# PR9003.net
KiCad netlist of a schematic drawn in EAGLE
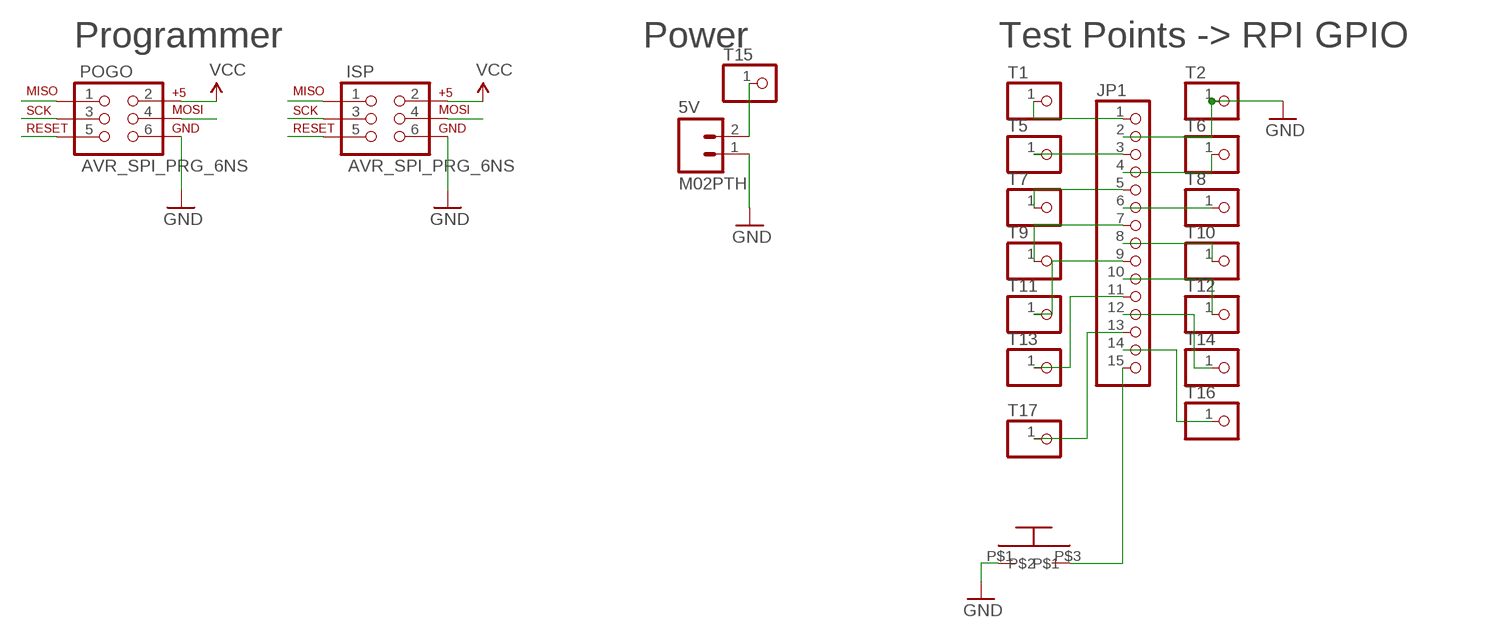
[diagram p0: schematic, sheet 1]

(export (version "E")
  (design (tool "Eeschema 10.0.6"))
  (components
    (comp (ref "5V")
      (value "M02PTH")
      (footprint "eagle-import:1X02")
      (libsource (lib "eagle-import") (part "M02PTH"))
    )
    (comp (ref "ISP")
      (value "AVR_SPI_PRG_6NS")
      (footprint "eagle-import:2X3-NS")
      (libsource (lib "eagle-import") (part "AVR_SPI_PRG_6NS"))
    )
    (comp (ref "JP1")
      (value "PINHD-1X15")
      (footprint "eagle-import:1X15")
      (libsource (lib "eagle-import") (part "PINHD-1X15"))
    )
    (comp (ref "POGO")
      (value "AVR_SPI_PRG_6NS")
      (footprint "eagle-import:2X3-NS")
      (libsource (lib "eagle-import") (part "AVR_SPI_PRG_6NS"))
    )
    (comp (ref "T1")
      (value "PINHD-1X1")
      (footprint "eagle-import:1X01")
      (libsource (lib "eagle-import") (part "PINHD-1X1"))
    )
    (comp (ref "T2")
      (value "PINHD-1X1")
      (footprint "eagle-import:1X01")
      (libsource (lib "eagle-import") (part "PINHD-1X1"))
    )
    (comp (ref "T5")
      (value "PINHD-1X1")
      (footprint "eagle-import:1X01")
      (libsource (lib "eagle-import") (part "PINHD-1X1"))
    )
    (comp (ref "T6")
      (value "PINHD-1X1")
      (footprint "eagle-import:1X01")
      (libsource (lib "eagle-import") (part "PINHD-1X1"))
    )
    (comp (ref "T7")
      (value "PINHD-1X1")
      (footprint "eagle-import:1X01")
      (libsource (lib "eagle-import") (part "PINHD-1X1"))
    )
    (comp (ref "T8")
      (value "PINHD-1X1")
      (footprint "eagle-import:1X01")
      (libsource (lib "eagle-import") (part "PINHD-1X1"))
    )
    (comp (ref "T9")
      (value "PINHD-1X1")
      (footprint "eagle-import:1X01")
      (libsource (lib "eagle-import") (part "PINHD-1X1"))
    )
    (comp (ref "T10")
      (value "PINHD-1X1")
      (footprint "eagle-import:1X01")
      (libsource (lib "eagle-import") (part "PINHD-1X1"))
    )
    (comp (ref "T11")
      (value "PINHD-1X1")
      (footprint "eagle-import:1X01")
      (libsource (lib "eagle-import") (part "PINHD-1X1"))
    )
    (comp (ref "T12")
      (value "PINHD-1X1")
      (footprint "eagle-import:1X01")
      (libsource (lib "eagle-import") (part "PINHD-1X1"))
    )
    (comp (ref "T13")
      (value "PINHD-1X1")
      (footprint "eagle-import:1X01")
      (libsource (lib "eagle-import") (part "PINHD-1X1"))
    )
    (comp (ref "T14")
      (value "PINHD-1X1")
      (footprint "eagle-import:1X01")
      (libsource (lib "eagle-import") (part "PINHD-1X1"))
    )
    (comp (ref "T15")
      (value "PINHD-1X1")
      (footprint "eagle-import:1X01")
      (libsource (lib "eagle-import") (part "PINHD-1X1"))
    )
    (comp (ref "T16")
      (value "PINHD-1X1")
      (footprint "eagle-import:1X01")
      (libsource (lib "eagle-import") (part "PINHD-1X1"))
    )
    (comp (ref "T17")
      (value "PINHD-1X1")
      (footprint "eagle-import:1X01")
      (libsource (lib "eagle-import") (part "PINHD-1X1"))
    )
    (comp (ref "U$1")
      (value "C&K_D6C_SWITCH")
      (footprint "eagle-import:C&K_D6C_SWITCH")
      (libsource (lib "eagle-import") (part "C&K_D6C_SWITCH"))
    )
  )
  (nets
    (net (code "1") (name "/MISO") (class "Default")
      (node (ref "ISP") (pin "1") (pinfunction "1_1") (pintype "passive"))
      (node (ref "POGO") (pin "1") (pinfunction "1_1") (pintype "passive"))
    )
    (net (code "2") (name "/MOSI") (class "Default")
      (node (ref "ISP") (pin "4") (pinfunction "4_4") (pintype "passive"))
      (node (ref "POGO") (pin "4") (pinfunction "4_4") (pintype "passive"))
    )
    (net (code "3") (name "/RESET") (class "Default")
      (node (ref "ISP") (pin "5") (pinfunction "5_5") (pintype "passive"))
      (node (ref "POGO") (pin "5") (pinfunction "5_5") (pintype "passive"))
    )
    (net (code "4") (name "/SCK") (class "Default")
      (node (ref "ISP") (pin "3") (pinfunction "3_3") (pintype "passive"))
      (node (ref "POGO") (pin "3") (pinfunction "3_3") (pintype "passive"))
    )
    (net (code "5") (name "GND") (class "Default")
      (node (ref "5V") (pin "1") (pinfunction "1_1") (pintype "passive"))
      (node (ref "ISP") (pin "6") (pinfunction "6_6") (pintype "passive"))
      (node (ref "JP1") (pin "2") (pinfunction "2_2") (pintype "passive"))
      (node (ref "POGO") (pin "6") (pinfunction "6_6") (pintype "passive"))
      (node (ref "T2") (pin "1") (pinfunction "1_1") (pintype "passive"))
      (node (ref "U$1") (pin "P$1") (pinfunction "P$1_P$1") (pintype "bidirectional"))
    )
    (net (code "6") (name "Net-(5V-Pad2)") (class "Default")
      (node (ref "5V") (pin "2") (pinfunction "2_2") (pintype "passive"))
      (node (ref "T15") (pin "1") (pinfunction "1_1") (pintype "passive"))
    )
    (net (code "7") (name "Net-(JP1-Pad1)") (class "Default")
      (node (ref "JP1") (pin "1") (pinfunction "1_1") (pintype "passive"))
      (node (ref "T1") (pin "1") (pinfunction "1_1") (pintype "passive"))
    )
    (net (code "8") (name "Net-(JP1-Pad3)") (class "Default")
      (node (ref "JP1") (pin "3") (pinfunction "3_3") (pintype "passive"))
      (node (ref "T5") (pin "1") (pinfunction "1_1") (pintype "passive"))
    )
    (net (code "9") (name "Net-(JP1-Pad4)") (class "Default")
      (node (ref "JP1") (pin "4") (pinfunction "4_4") (pintype "passive"))
      (node (ref "T6") (pin "1") (pinfunction "1_1") (pintype "passive"))
    )
    (net (code "10") (name "Net-(JP1-Pad5)") (class "Default")
      (node (ref "JP1") (pin "5") (pinfunction "5_5") (pintype "passive"))
      (node (ref "T7") (pin "1") (pinfunction "1_1") (pintype "passive"))
    )
    (net (code "11") (name "Net-(JP1-Pad6)") (class "Default")
      (node (ref "JP1") (pin "6") (pinfunction "6_6") (pintype "passive"))
      (node (ref "T8") (pin "1") (pinfunction "1_1") (pintype "passive"))
    )
    (net (code "12") (name "Net-(JP1-Pad7)") (class "Default")
      (node (ref "JP1") (pin "7") (pinfunction "7_7") (pintype "passive"))
      (node (ref "T9") (pin "1") (pinfunction "1_1") (pintype "passive"))
    )
    (net (code "13") (name "Net-(JP1-Pad8)") (class "Default")
      (node (ref "JP1") (pin "8") (pinfunction "8_8") (pintype "passive"))
      (node (ref "T10") (pin "1") (pinfunction "1_1") (pintype "passive"))
    )
    (net (code "14") (name "Net-(JP1-Pad9)") (class "Default")
      (node (ref "JP1") (pin "9") (pinfunction "9_9") (pintype "passive"))
      (node (ref "T11") (pin "1") (pinfunction "1_1") (pintype "passive"))
    )
    (net (code "15") (name "Net-(JP1-Pad10)") (class "Default")
      (node (ref "JP1") (pin "10") (pinfunction "10_10") (pintype "passive"))
      (node (ref "T12") (pin "1") (pinfunction "1_1") (pintype "passive"))
    )
    (net (code "16") (name "Net-(JP1-Pad11)") (class "Default")
      (node (ref "JP1") (pin "11") (pinfunction "11_11") (pintype "passive"))
      (node (ref "T13") (pin "1") (pinfunction "1_1") (pintype "passive"))
    )
    (net (code "17") (name "Net-(JP1-Pad12)") (class "Default")
      (node (ref "JP1") (pin "12") (pinfunction "12_12") (pintype "passive"))
      (node (ref "T14") (pin "1") (pinfunction "1_1") (pintype "passive"))
    )
    (net (code "18") (name "Net-(JP1-Pad13)") (class "Default")
      (node (ref "JP1") (pin "13") (pinfunction "13_13") (pintype "passive"))
      (node (ref "T17") (pin "1") (pinfunction "1_1") (pintype "passive"))
    )
    (net (code "19") (name "Net-(JP1-Pad14)") (class "Default")
      (node (ref "JP1") (pin "14") (pinfunction "14_14") (pintype "passive"))
      (node (ref "T16") (pin "1") (pinfunction "1_1") (pintype "passive"))
    )
    (net (code "20") (name "Net-(U$1-P$2)") (class "Default")
      (node (ref "JP1") (pin "15") (pinfunction "15_15") (pintype "passive"))
      (node (ref "U$1") (pin "P$3") (pinfunction "P$2_P$3") (pintype "bidirectional"))
    )
    (net (code "21") (name "VCC") (class "Default")
      (node (ref "ISP") (pin "2") (pinfunction "2_2") (pintype "passive"))
      (node (ref "POGO") (pin "2") (pinfunction "2_2") (pintype "passive"))
    )
  )
)
